# RCShield-v2.net
KiCad netlist of a schematic drawn in EAGLE
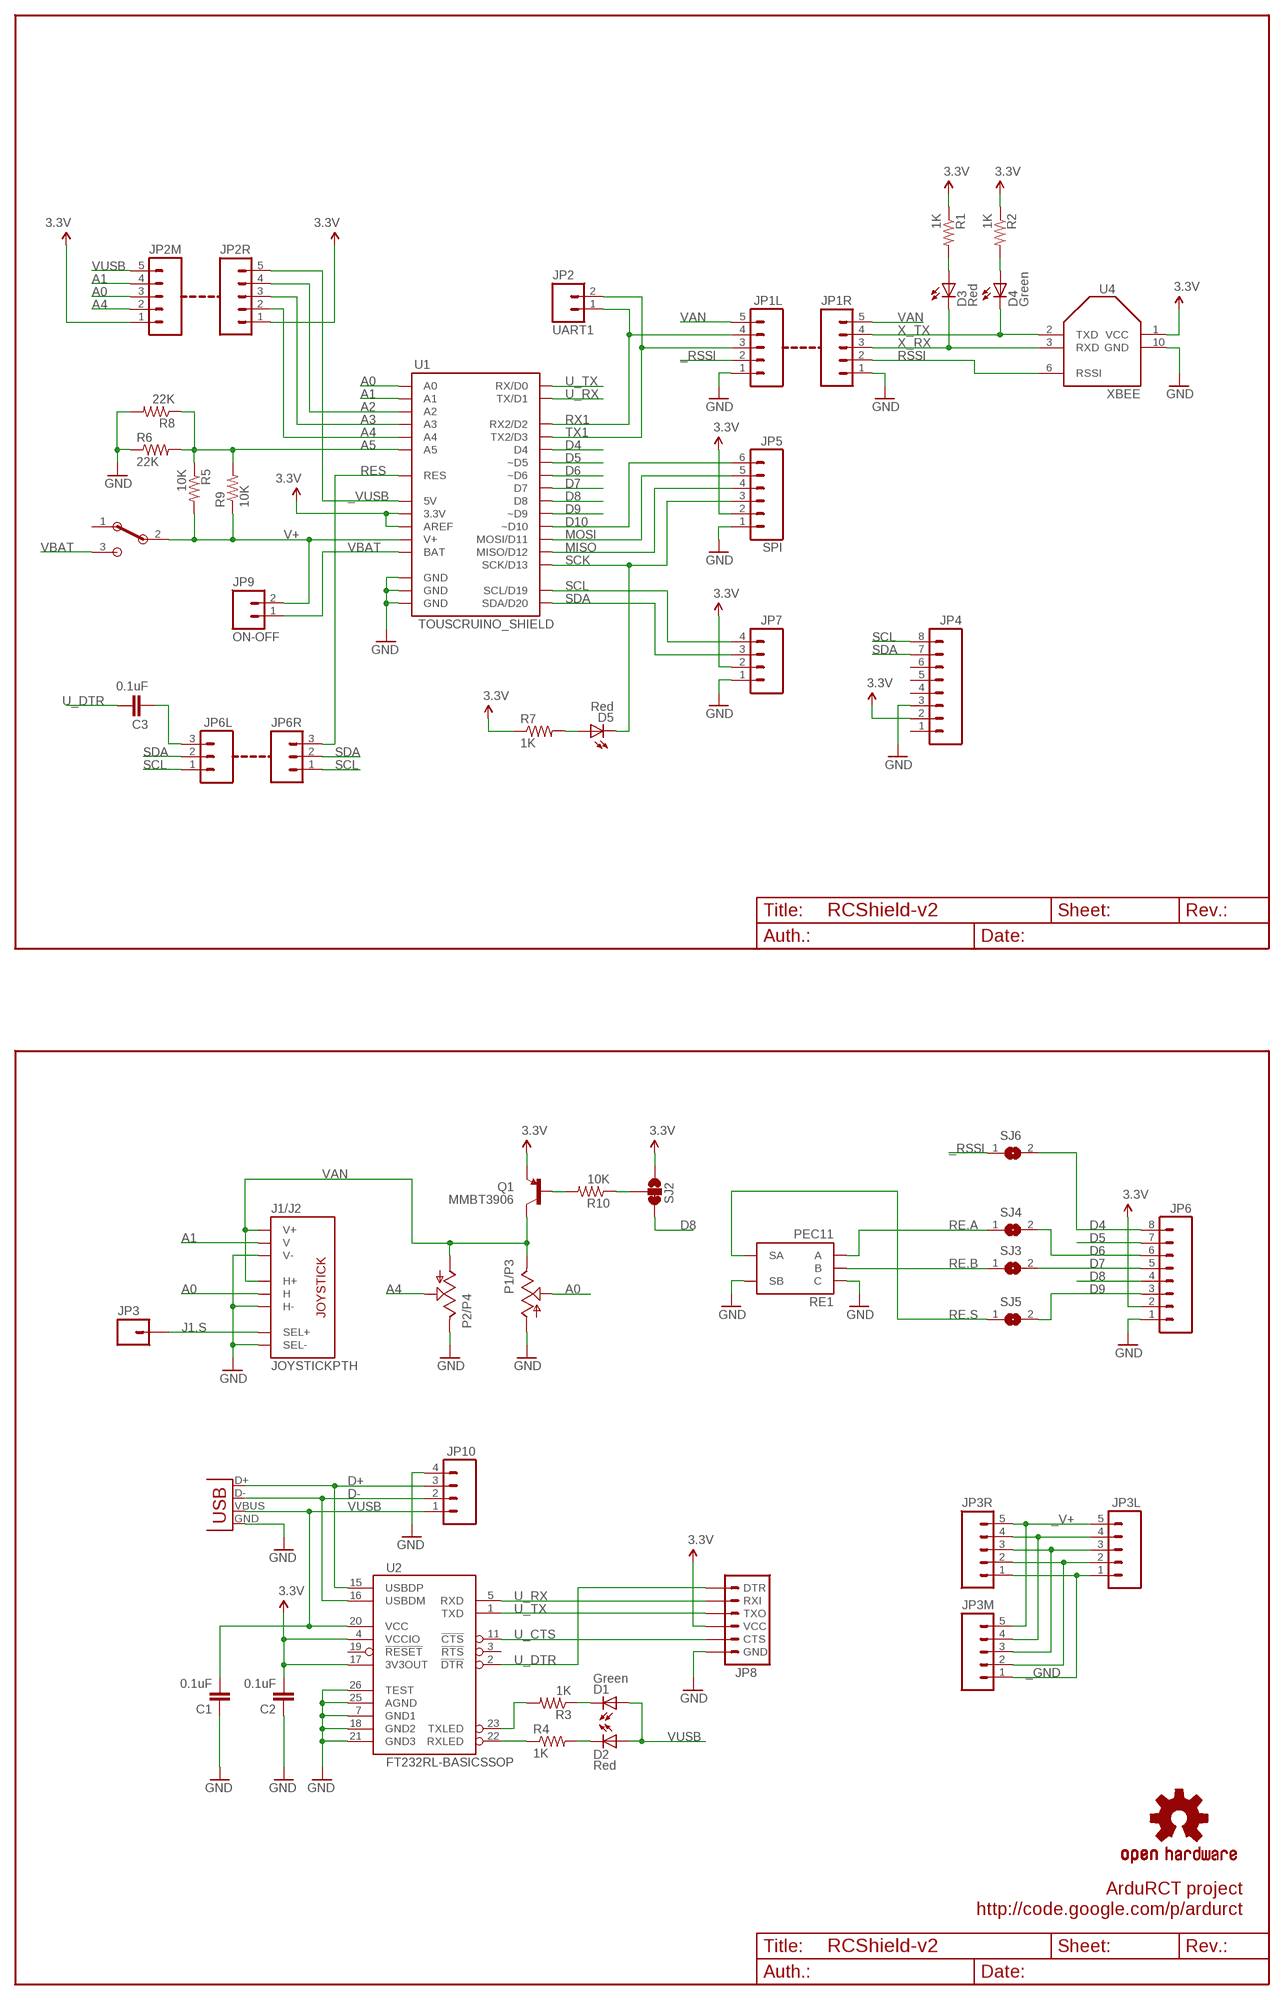
[diagram p0: schematic, sheet 1]

(export (version "E")
  (design (tool "Eeschema 10.0.6"))
  (components
    (comp (ref "C1")
      (value "0.1uF")
      (footprint "eagle-import:0805")
      (libsource (lib "eagle-import") (part "CAP0805"))
    )
    (comp (ref "C2")
      (value "0.1uF")
      (footprint "eagle-import:0805")
      (libsource (lib "eagle-import") (part "CAP0805"))
    )
    (comp (ref "C3")
      (value "0.1uF")
      (footprint "eagle-import:0805")
      (libsource (lib "eagle-import") (part "CAP0805"))
    )
    (comp (ref "D1")
      (value "Green")
      (footprint "eagle-import:LED")
      (libsource (lib "eagle-import") (part "LED"))
    )
    (comp (ref "D2")
      (value "Red")
      (footprint "eagle-import:LED")
      (libsource (lib "eagle-import") (part "LED"))
    )
    (comp (ref "D3")
      (value "Red")
      (footprint "eagle-import:LED")
      (libsource (lib "eagle-import") (part "LED"))
    )
    (comp (ref "D4")
      (value "Green")
      (footprint "eagle-import:LED")
      (libsource (lib "eagle-import") (part "LED"))
    )
    (comp (ref "D5")
      (value "Red")
      (footprint "eagle-import:LED")
      (libsource (lib "eagle-import") (part "LED"))
    )
    (comp (ref "J1/J2")
      (value "JOYSTICKPTH")
      (footprint "eagle-import:JOYSTICK")
      (libsource (lib "eagle-import") (part "JOYSTICKPTH"))
    )
    (comp (ref "JP1L")
      (value "M05")
      (footprint "eagle-import:2+3")
      (libsource (lib "eagle-import") (part "M05"))
    )
    (comp (ref "JP1R")
      (value "M05")
      (footprint "eagle-import:2+3")
      (libsource (lib "eagle-import") (part "M05"))
    )
    (comp (ref "JP2")
      (value "UART1")
      (footprint "eagle-import:1X02")
      (libsource (lib "eagle-import") (part "M02"))
    )
    (comp (ref "JP2M")
      (value "M05")
      (footprint "eagle-import:2+3")
      (libsource (lib "eagle-import") (part "M05"))
    )
    (comp (ref "JP2R")
      (value "M05")
      (footprint "eagle-import:2+3")
      (libsource (lib "eagle-import") (part "M05"))
    )
    (comp (ref "JP3")
      (value "M01PTH")
      (footprint "eagle-import:1X01")
      (libsource (lib "eagle-import") (part "M01PTH"))
    )
    (comp (ref "JP3L")
      (value "M05")
      (footprint "eagle-import:2+3")
      (libsource (lib "eagle-import") (part "M05"))
    )
    (comp (ref "JP3M")
      (value "M05")
      (footprint "eagle-import:2+3")
      (libsource (lib "eagle-import") (part "M05"))
    )
    (comp (ref "JP3R")
      (value "M05")
      (footprint "eagle-import:2+3")
      (libsource (lib "eagle-import") (part "M05"))
    )
    (comp (ref "JP4")
      (value "M08")
      (footprint "eagle-import:1X08")
      (libsource (lib "eagle-import") (part "M08"))
    )
    (comp (ref "JP5")
      (value "SPI")
      (footprint "eagle-import:1X06")
      (libsource (lib "eagle-import") (part "M06SIP"))
    )
    (comp (ref "JP6")
      (value "M08")
      (footprint "eagle-import:1X08")
      (libsource (lib "eagle-import") (part "M08"))
    )
    (comp (ref "JP6L")
      (value "M03PTH")
      (footprint "eagle-import:1X03")
      (libsource (lib "eagle-import") (part "M03PTH"))
    )
    (comp (ref "JP6R")
      (value "M03PTH")
      (footprint "eagle-import:1X03")
      (libsource (lib "eagle-import") (part "M03PTH"))
    )
    (comp (ref "JP7")
      (value "M04")
      (footprint "eagle-import:1X04")
      (libsource (lib "eagle-import") (part "M04"))
    )
    (comp (ref "JP8")
      (value "ARDUINO_SERIAL_PROGRAM")
      (footprint "eagle-import:1X06_F")
      (libsource (lib "eagle-import") (part "ARDUINO_SERIAL_PROGRAM"))
    )
    (comp (ref "JP9")
      (value "ON-OFF")
      (footprint "eagle-import:1X02")
      (libsource (lib "eagle-import") (part "M02"))
    )
    (comp (ref "JP10")
      (value "M04")
      (footprint "eagle-import:1X04")
      (libsource (lib "eagle-import") (part "M04"))
    )
    (comp (ref "P1/P3")
      (value "POT")
      (footprint "eagle-import:ALPS_POT")
      (libsource (lib "eagle-import") (part "POT"))
    )
    (comp (ref "P2/P4")
      (value "POT")
      (footprint "eagle-import:ALPS_POT")
      (libsource (lib "eagle-import") (part "POT"))
    )
    (comp (ref "Q1")
      (value "MMBT3906")
      (footprint "eagle-import:SOT23-3")
      (libsource (lib "eagle-import") (part "TRANSISTOR_PNPSMD"))
    )
    (comp (ref "R1")
      (value "1K")
      (footprint "eagle-import:0805")
      (libsource (lib "eagle-import") (part "RESISTOR0805-RES"))
    )
    (comp (ref "R2")
      (value "1K")
      (footprint "eagle-import:0805")
      (libsource (lib "eagle-import") (part "RESISTOR0805-RES"))
    )
    (comp (ref "R3")
      (value "1K")
      (footprint "eagle-import:0805")
      (libsource (lib "eagle-import") (part "RESISTOR0805-RES"))
    )
    (comp (ref "R4")
      (value "1K")
      (footprint "eagle-import:0805")
      (libsource (lib "eagle-import") (part "RESISTOR0805-RES"))
    )
    (comp (ref "R5")
      (value "10K")
      (footprint "eagle-import:0805")
      (libsource (lib "eagle-import") (part "RESISTOR0805-RES"))
    )
    (comp (ref "R6")
      (value "22K")
      (footprint "eagle-import:0805")
      (libsource (lib "eagle-import") (part "RESISTOR0805-RES"))
    )
    (comp (ref "R7")
      (value "1K")
      (footprint "eagle-import:0805")
      (libsource (lib "eagle-import") (part "RESISTOR0805-RES"))
    )
    (comp (ref "R8")
      (value "22K")
      (footprint "eagle-import:0207_7")
      (libsource (lib "eagle-import") (part "R-US_0207/7"))
    )
    (comp (ref "R9")
      (value "10K")
      (footprint "eagle-import:0207_7")
      (libsource (lib "eagle-import") (part "R-US_0207/7"))
    )
    (comp (ref "R10")
      (value "10K")
      (footprint "eagle-import:0805")
      (libsource (lib "eagle-import") (part "RESISTOR0805-RES"))
    )
    (comp (ref "RE1")
      (value "PEC11")
      (footprint "eagle-import:PEC11")
      (libsource (lib "eagle-import") (part "PEC11"))
    )
    (comp (ref "S4")
      (value "EG1224")
      (footprint "eagle-import:EG1224")
      (libsource (lib "eagle-import") (part "EG1224"))
    )
    (comp (ref "SJ2")
      (value "SJ_2WAYS_1-2W")
      (footprint "eagle-import:SJ_2WAYS_1-2")
      (libsource (lib "eagle-import") (part "SJ_2WAYS_1-2W"))
    )
    (comp (ref "SJ3") (value "SJ") (footprint "eagle-import:SJ") (libsource (lib "eagle-import") (part "SJ")))
    (comp (ref "SJ4") (value "SJ") (footprint "eagle-import:SJ") (libsource (lib "eagle-import") (part "SJ")))
    (comp (ref "SJ5") (value "SJ") (footprint "eagle-import:SJ") (libsource (lib "eagle-import") (part "SJ")))
    (comp (ref "SJ6") (value "SJ") (footprint "eagle-import:SJ") (libsource (lib "eagle-import") (part "SJ")))
    (comp (ref "U$1")
      (value "OSHW-LOGOM")
      (footprint "eagle-import:OSHW-LOGO-M")
      (libsource (lib "eagle-import") (part "OSHW-LOGOM"))
    )
    (comp (ref "U1")
      (value "TOUSCRUINO_SHIELD")
      (footprint "eagle-import:TOUSCRUINO_SHIELD_SPLIT")
      (libsource (lib "eagle-import") (part "TOUSCRUINO_SHIELDSPLIT"))
    )
    (comp (ref "U2")
      (value "FT232RL-BASICSSOP")
      (footprint "eagle-import:SSOP28DB")
      (libsource (lib "eagle-import") (part "FT232RL-BASICSSOP"))
    )
    (comp (ref "U4")
      (value "XBEE")
      (footprint "eagle-import:XBEE-SMD")
      (libsource (lib "eagle-import") (part "XBEE-RSSI"))
    )
    (comp (ref "X1")
      (value "USBSMD")
      (footprint "eagle-import:USB-MINIB")
      (libsource (lib "eagle-import") (part "USBSMD"))
    )
  )
  (nets
    (net (code "1") (name "/A0") (class "Default")
      (node (ref "J1/J2") (pin "H2") (pinfunction "H_H2") (pintype "bidirectional"))
      (node (ref "JP2M") (pin "3") (pinfunction "3_3") (pintype "passive"))
      (node (ref "P1/P3") (pin "P$2") (pinfunction "S_P$2") (pintype "passive"))
      (node (ref "U1") (pin "A0") (pinfunction "A0_A0") (pintype "bidirectional"))
    )
    (net (code "2") (name "/A1") (class "Default")
      (node (ref "J1/J2") (pin "V2") (pinfunction "V_V2") (pintype "bidirectional"))
      (node (ref "JP2M") (pin "4") (pinfunction "4_4") (pintype "passive"))
      (node (ref "U1") (pin "A1") (pinfunction "A1_A1") (pintype "bidirectional"))
    )
    (net (code "3") (name "/A2") (class "Default")
      (node (ref "JP2R") (pin "4") (pinfunction "4_4") (pintype "passive"))
      (node (ref "U1") (pin "A2") (pinfunction "A2_A2") (pintype "bidirectional"))
    )
    (net (code "4") (name "/A3") (class "Default")
      (node (ref "JP2R") (pin "3") (pinfunction "3_3") (pintype "passive"))
      (node (ref "U1") (pin "A3") (pinfunction "A3_A3") (pintype "bidirectional"))
    )
    (net (code "5") (name "/A4") (class "Default")
      (node (ref "JP2M") (pin "2") (pinfunction "2_2") (pintype "passive"))
      (node (ref "JP2R") (pin "2") (pinfunction "2_2") (pintype "passive"))
      (node (ref "P2/P4") (pin "P$2") (pinfunction "S_P$2") (pintype "passive"))
      (node (ref "U1") (pin "A4") (pinfunction "A4_A4") (pintype "bidirectional"))
    )
    (net (code "6") (name "/A5") (class "Default")
      (node (ref "R5") (pin "1") (pinfunction "1_1") (pintype "passive"))
      (node (ref "R6") (pin "2") (pinfunction "2_2") (pintype "passive"))
      (node (ref "R8") (pin "1") (pinfunction "1_1") (pintype "passive"))
      (node (ref "R9") (pin "2") (pinfunction "2_2") (pintype "passive"))
      (node (ref "U1") (pin "A5") (pinfunction "A5_A5") (pintype "bidirectional"))
    )
    (net (code "7") (name "/D+") (class "Default")
      (node (ref "JP10") (pin "3") (pinfunction "3_3") (pintype "passive"))
      (node (ref "U2") (pin "15") (pinfunction "USBDP_15") (pintype "bidirectional"))
      (node (ref "X1") (pin "D+") (pinfunction "D+_D+") (pintype "bidirectional"))
    )
    (net (code "8") (name "/D-") (class "Default")
      (node (ref "JP10") (pin "2") (pinfunction "2_2") (pintype "passive"))
      (node (ref "U2") (pin "16") (pinfunction "USBDM_16") (pintype "bidirectional"))
      (node (ref "X1") (pin "D-") (pinfunction "D-_D-") (pintype "bidirectional"))
    )
    (net (code "9") (name "/D4") (class "Default")
      (node (ref "JP6") (pin "8") (pinfunction "8_8") (pintype "passive"))
      (node (ref "SJ6") (pin "2") (pinfunction "2_2") (pintype "passive"))
      (node (ref "U1") (pin "D4") (pinfunction "D4_D4") (pintype "bidirectional"))
    )
    (net (code "10") (name "/D5") (class "Default")
      (node (ref "JP6") (pin "7") (pinfunction "7_7") (pintype "passive"))
      (node (ref "U1") (pin "D5") (pinfunction "~{D5}_D5") (pintype "bidirectional"))
    )
    (net (code "11") (name "/D6") (class "Default")
      (node (ref "JP6") (pin "6") (pinfunction "6_6") (pintype "passive"))
      (node (ref "SJ4") (pin "2") (pinfunction "2_2") (pintype "passive"))
      (node (ref "U1") (pin "D6") (pinfunction "~{D6}_D6") (pintype "bidirectional"))
    )
    (net (code "12") (name "/D7") (class "Default")
      (node (ref "JP6") (pin "5") (pinfunction "5_5") (pintype "passive"))
      (node (ref "SJ3") (pin "2") (pinfunction "2_2") (pintype "passive"))
      (node (ref "U1") (pin "D7") (pinfunction "D7_D7") (pintype "bidirectional"))
    )
    (net (code "13") (name "/D8") (class "Default")
      (node (ref "JP6") (pin "4") (pinfunction "4_4") (pintype "passive"))
      (node (ref "SJ2") (pin "1") (pinfunction "1_1") (pintype "passive"))
      (node (ref "U1") (pin "D8") (pinfunction "D8_D8") (pintype "bidirectional"))
    )
    (net (code "14") (name "/D9") (class "Default")
      (node (ref "JP6") (pin "3") (pinfunction "3_3") (pintype "passive"))
      (node (ref "SJ5") (pin "2") (pinfunction "2_2") (pintype "passive"))
      (node (ref "U1") (pin "D9") (pinfunction "~{D9}_D9") (pintype "bidirectional"))
    )
    (net (code "15") (name "/D10") (class "Default")
      (node (ref "JP5") (pin "6") (pinfunction "6_6") (pintype "passive"))
      (node (ref "U1") (pin "D10") (pinfunction "~{D10}_D10") (pintype "bidirectional"))
    )
    (net (code "16") (name "/J1.S") (class "Default")
      (node (ref "J1/J2") (pin "B1A") (pinfunction "SEL+_B1A") (pintype "bidirectional"))
      (node (ref "JP3") (pin "1") (pinfunction "1_1") (pintype "passive"))
    )
    (net (code "17") (name "/MISO") (class "Default")
      (node (ref "JP5") (pin "4") (pinfunction "4_4") (pintype "passive"))
      (node (ref "U1") (pin "D12") (pinfunction "MISO/D12_D12") (pintype "bidirectional"))
    )
    (net (code "18") (name "/MOSI") (class "Default")
      (node (ref "JP5") (pin "5") (pinfunction "5_5") (pintype "passive"))
      (node (ref "U1") (pin "D11") (pinfunction "MOSI/D11_D11") (pintype "bidirectional"))
    )
    (net (code "19") (name "/RE.A") (class "Default")
      (node (ref "RE1") (pin "A") (pinfunction "A_A") (pintype "bidirectional"))
      (node (ref "SJ4") (pin "1") (pinfunction "1_1") (pintype "passive"))
    )
    (net (code "20") (name "/RE.B") (class "Default")
      (node (ref "RE1") (pin "B") (pinfunction "B_B") (pintype "bidirectional"))
      (node (ref "SJ3") (pin "1") (pinfunction "1_1") (pintype "passive"))
    )
    (net (code "21") (name "/RE.S") (class "Default")
      (node (ref "RE1") (pin "S1") (pinfunction "SA_S1") (pintype "bidirectional"))
      (node (ref "SJ5") (pin "1") (pinfunction "1_1") (pintype "passive"))
    )
    (net (code "22") (name "/RES") (class "Default")
      (node (ref "JP6R") (pin "3") (pinfunction "3_3") (pintype "passive"))
      (node (ref "U1") (pin "RES") (pinfunction "RES_RES") (pintype "bidirectional"))
    )
    (net (code "23") (name "/RSSI") (class "Default")
      (node (ref "JP1R") (pin "2") (pinfunction "2_2") (pintype "passive"))
      (node (ref "U4") (pin "6") (pinfunction "RSSI_6") (pintype "bidirectional"))
    )
    (net (code "24") (name "/RX1") (class "Default")
      (node (ref "JP1L") (pin "4") (pinfunction "4_4") (pintype "passive"))
      (node (ref "JP2") (pin "1") (pinfunction "1_1") (pintype "passive"))
      (node (ref "U1") (pin "D2") (pinfunction "RX2/D2_D2") (pintype "bidirectional"))
    )
    (net (code "25") (name "/SCK") (class "Default")
      (node (ref "D5") (pin "C1") (pinfunction "C_C1") (pintype "passive"))
      (node (ref "JP5") (pin "3") (pinfunction "3_3") (pintype "passive"))
      (node (ref "U1") (pin "D13") (pinfunction "SCK/D13_D13") (pintype "bidirectional"))
    )
    (net (code "26") (name "/SCL") (class "Default")
      (node (ref "JP4") (pin "8") (pinfunction "8_8") (pintype "passive"))
      (node (ref "JP6L") (pin "1") (pinfunction "1_1") (pintype "passive"))
      (node (ref "JP6R") (pin "1") (pinfunction "1_1") (pintype "passive"))
      (node (ref "JP7") (pin "4") (pinfunction "4_4") (pintype "passive"))
      (node (ref "U1") (pin "SCL") (pinfunction "SCL/D19_SCL") (pintype "bidirectional"))
    )
    (net (code "27") (name "/SDA") (class "Default")
      (node (ref "JP4") (pin "7") (pinfunction "7_7") (pintype "passive"))
      (node (ref "JP6L") (pin "2") (pinfunction "2_2") (pintype "passive"))
      (node (ref "JP6R") (pin "2") (pinfunction "2_2") (pintype "passive"))
      (node (ref "JP7") (pin "3") (pinfunction "3_3") (pintype "passive"))
      (node (ref "U1") (pin "SDA") (pinfunction "SDA/D20_SDA") (pintype "bidirectional"))
    )
    (net (code "28") (name "/TX1") (class "Default")
      (node (ref "JP1L") (pin "3") (pinfunction "3_3") (pintype "passive"))
      (node (ref "JP2") (pin "2") (pinfunction "2_2") (pintype "passive"))
      (node (ref "U1") (pin "D3") (pinfunction "TX2/D3_D3") (pintype "bidirectional"))
    )
    (net (code "29") (name "/U_CTS") (class "Default")
      (node (ref "JP8") (pin "5") (pinfunction "CTS_5") (pintype "passive"))
      (node (ref "U2") (pin "11") (pinfunction "~{CTS}_11") (pintype "bidirectional"))
    )
    (net (code "30") (name "/U_DTR") (class "Default")
      (node (ref "C3") (pin "1") (pinfunction "1_1") (pintype "passive"))
      (node (ref "JP8") (pin "1") (pinfunction "DTR_1") (pintype "passive"))
      (node (ref "U2") (pin "2") (pinfunction "~{DTR}_2") (pintype "bidirectional"))
    )
    (net (code "31") (name "/U_RX") (class "Default")
      (node (ref "JP8") (pin "2") (pinfunction "RXI_2") (pintype "passive"))
      (node (ref "U1") (pin "TX") (pinfunction "TX/D1_TX") (pintype "bidirectional"))
      (node (ref "U2") (pin "5") (pinfunction "RXD_5") (pintype "input"))
    )
    (net (code "32") (name "/U_TX") (class "Default")
      (node (ref "JP8") (pin "3") (pinfunction "TXO_3") (pintype "passive"))
      (node (ref "U1") (pin "RX") (pinfunction "RX/D0_RX") (pintype "bidirectional"))
      (node (ref "U2") (pin "1") (pinfunction "TXD_1") (pintype "output"))
    )
    (net (code "33") (name "/V+") (class "Default")
      (node (ref "JP9") (pin "2") (pinfunction "2_2") (pintype "passive"))
      (node (ref "R5") (pin "2") (pinfunction "2_2") (pintype "passive"))
      (node (ref "R9") (pin "1") (pinfunction "1_1") (pintype "passive"))
      (node (ref "S4") (pin "2") (pinfunction "2_2") (pintype "bidirectional"))
      (node (ref "U1") (pin "V+") (pinfunction "V+_V+") (pintype "bidirectional"))
    )
    (net (code "34") (name "/VAN") (class "Default")
      (node (ref "J1/J2") (pin "H1") (pinfunction "H+_H1") (pintype "bidirectional"))
      (node (ref "J1/J2") (pin "V1") (pinfunction "V+_V1") (pintype "bidirectional"))
      (node (ref "JP1L") (pin "5") (pinfunction "5_5") (pintype "passive"))
      (node (ref "JP1R") (pin "5") (pinfunction "5_5") (pintype "passive"))
      (node (ref "P1/P3") (pin "P$1") (pinfunction "E_P$1") (pintype "passive"))
      (node (ref "P2/P4") (pin "P$3") (pinfunction "A_P$3") (pintype "passive"))
      (node (ref "Q1") (pin "3") (pinfunction "C_3") (pintype "passive"))
    )
    (net (code "35") (name "/VBAT") (class "Default")
      (node (ref "JP9") (pin "1") (pinfunction "1_1") (pintype "passive"))
      (node (ref "S4") (pin "3") (pinfunction "3_3") (pintype "bidirectional"))
      (node (ref "U1") (pin "BAT") (pinfunction "BAT_BAT") (pintype "bidirectional"))
    )
    (net (code "36") (name "/VUSB") (class "Default")
      (node (ref "C1") (pin "2") (pinfunction "2_2") (pintype "passive"))
      (node (ref "D1") (pin "A1") (pinfunction "A_A1") (pintype "passive"))
      (node (ref "D2") (pin "A1") (pinfunction "A_A1") (pintype "passive"))
      (node (ref "JP10") (pin "1") (pinfunction "1_1") (pintype "passive"))
      (node (ref "JP2M") (pin "5") (pinfunction "5_5") (pintype "passive"))
      (node (ref "U2") (pin "20") (pinfunction "VCC_20") (pintype "bidirectional"))
      (node (ref "X1") (pin "VBUS") (pinfunction "VBUS_VBUS") (pintype "bidirectional"))
    )
    (net (code "37") (name "/X_RX") (class "Default")
      (node (ref "D3") (pin "C1") (pinfunction "C_C1") (pintype "passive"))
      (node (ref "JP1R") (pin "3") (pinfunction "3_3") (pintype "passive"))
      (node (ref "U4") (pin "3") (pinfunction "RXD_3") (pintype "bidirectional"))
    )
    (net (code "38") (name "/X_TX") (class "Default")
      (node (ref "D4") (pin "C1") (pinfunction "C_C1") (pintype "passive"))
      (node (ref "JP1R") (pin "4") (pinfunction "4_4") (pintype "passive"))
      (node (ref "U4") (pin "2") (pinfunction "TXD_2") (pintype "bidirectional"))
    )
    (net (code "39") (name "/_GND") (class "Default")
      (node (ref "JP3L") (pin "1") (pinfunction "1_1") (pintype "passive"))
      (node (ref "JP3M") (pin "1") (pinfunction "1_1") (pintype "passive"))
      (node (ref "JP3R") (pin "1") (pinfunction "1_1") (pintype "passive"))
    )
    (net (code "40") (name "/_RSSI") (class "Default")
      (node (ref "JP1L") (pin "2") (pinfunction "2_2") (pintype "passive"))
      (node (ref "SJ6") (pin "1") (pinfunction "1_1") (pintype "passive"))
    )
    (net (code "41") (name "/_V+") (class "Default")
      (node (ref "JP3L") (pin "5") (pinfunction "5_5") (pintype "passive"))
      (node (ref "JP3M") (pin "5") (pinfunction "5_5") (pintype "passive"))
      (node (ref "JP3R") (pin "5") (pinfunction "5_5") (pintype "passive"))
    )
    (net (code "42") (name "/_VUSB") (class "Default")
      (node (ref "JP2R") (pin "5") (pinfunction "5_5") (pintype "passive"))
      (node (ref "U1") (pin "5V") (pinfunction "5V_5V") (pintype "bidirectional"))
    )
    (net (code "43") (name "3.3V") (class "Default")
      (node (ref "C2") (pin "2") (pinfunction "2_2") (pintype "passive"))
      (node (ref "JP2M") (pin "1") (pinfunction "1_1") (pintype "passive"))
      (node (ref "JP2R") (pin "1") (pinfunction "1_1") (pintype "passive"))
      (node (ref "JP4") (pin "2") (pinfunction "2_2") (pintype "passive"))
      (node (ref "JP5") (pin "2") (pinfunction "2_2") (pintype "passive"))
      (node (ref "JP6") (pin "2") (pinfunction "2_2") (pintype "passive"))
      (node (ref "JP7") (pin "2") (pinfunction "2_2") (pintype "passive"))
      (node (ref "JP8") (pin "4") (pinfunction "VCC_4") (pintype "passive"))
      (node (ref "Q1") (pin "2") (pinfunction "E_2") (pintype "passive"))
      (node (ref "R1") (pin "1") (pinfunction "1_1") (pintype "passive"))
      (node (ref "R2") (pin "1") (pinfunction "1_1") (pintype "passive"))
      (node (ref "R7") (pin "1") (pinfunction "1_1") (pintype "passive"))
      (node (ref "SJ2") (pin "3") (pinfunction "3_3") (pintype "passive"))
      (node (ref "U1") (pin "3.3V") (pinfunction "3.3V_3.3V") (pintype "bidirectional"))
      (node (ref "U1") (pin "AREF") (pinfunction "AREF_AREF") (pintype "bidirectional"))
      (node (ref "U2") (pin "17") (pinfunction "3V3OUT_17") (pintype "output"))
      (node (ref "U2") (pin "4") (pinfunction "VCCIO_4") (pintype "bidirectional"))
      (node (ref "U4") (pin "1") (pinfunction "VCC_1") (pintype "bidirectional"))
    )
    (net (code "44") (name "GND") (class "Default")
      (node (ref "C1") (pin "1") (pinfunction "1_1") (pintype "passive"))
      (node (ref "C2") (pin "1") (pinfunction "1_1") (pintype "passive"))
      (node (ref "J1/J2") (pin "B2A") (pinfunction "SEL-_B2A") (pintype "bidirectional"))
      (node (ref "J1/J2") (pin "H3") (pinfunction "H-_H3") (pintype "bidirectional"))
      (node (ref "J1/J2") (pin "V3") (pinfunction "V-_V3") (pintype "bidirectional"))
      (node (ref "JP10") (pin "4") (pinfunction "4_4") (pintype "passive"))
      (node (ref "JP1L") (pin "1") (pinfunction "1_1") (pintype "passive"))
      (node (ref "JP1R") (pin "1") (pinfunction "1_1") (pintype "passive"))
      (node (ref "JP4") (pin "3") (pinfunction "3_3") (pintype "passive"))
      (node (ref "JP5") (pin "1") (pinfunction "1_1") (pintype "passive"))
      (node (ref "JP6") (pin "1") (pinfunction "1_1") (pintype "passive"))
      (node (ref "JP7") (pin "1") (pinfunction "1_1") (pintype "passive"))
      (node (ref "JP8") (pin "6") (pinfunction "GND_6") (pintype "passive"))
      (node (ref "P1/P3") (pin "P$3") (pinfunction "A_P$3") (pintype "passive"))
      (node (ref "P2/P4") (pin "P$1") (pinfunction "E_P$1") (pintype "passive"))
      (node (ref "R6") (pin "1") (pinfunction "1_1") (pintype "passive"))
      (node (ref "R8") (pin "2") (pinfunction "2_2") (pintype "passive"))
      (node (ref "RE1") (pin "C") (pinfunction "C_C") (pintype "bidirectional"))
      (node (ref "RE1") (pin "S2") (pinfunction "SB_S2") (pintype "bidirectional"))
      (node (ref "U1") (pin "GND@0") (pinfunction "GND_GND@0") (pintype "bidirectional"))
      (node (ref "U1") (pin "GND@1") (pinfunction "GND_GND@1") (pintype "bidirectional"))
      (node (ref "U1") (pin "GND@2") (pinfunction "GND_GND@2") (pintype "bidirectional"))
      (node (ref "U2") (pin "18") (pinfunction "GND2_18") (pintype "bidirectional"))
      (node (ref "U2") (pin "21") (pinfunction "GND3_21") (pintype "bidirectional"))
      (node (ref "U2") (pin "25") (pinfunction "AGND_25") (pintype "bidirectional"))
      (node (ref "U2") (pin "26") (pinfunction "TEST_26") (pintype "input"))
      (node (ref "U2") (pin "7") (pinfunction "GND1_7") (pintype "bidirectional"))
      (node (ref "U4") (pin "10") (pinfunction "GND_10") (pintype "bidirectional"))
      (node (ref "X1") (pin "GND") (pinfunction "GND_GND") (pintype "bidirectional"))
    )
    (net (code "45") (name "Net-(C3-Pad2)") (class "Default")
      (node (ref "C3") (pin "2") (pinfunction "2_2") (pintype "passive"))
      (node (ref "JP6L") (pin "3") (pinfunction "3_3") (pintype "passive"))
    )
    (net (code "46") (name "Net-(D1-C)") (class "Default")
      (node (ref "D1") (pin "C1") (pinfunction "C_C1") (pintype "passive"))
      (node (ref "R3") (pin "1") (pinfunction "1_1") (pintype "passive"))
    )
    (net (code "47") (name "Net-(D2-C)") (class "Default")
      (node (ref "D2") (pin "C1") (pinfunction "C_C1") (pintype "passive"))
      (node (ref "R4") (pin "2") (pinfunction "2_2") (pintype "passive"))
    )
    (net (code "48") (name "Net-(D3-A)") (class "Default")
      (node (ref "D3") (pin "A1") (pinfunction "A_A1") (pintype "passive"))
      (node (ref "R1") (pin "2") (pinfunction "2_2") (pintype "passive"))
    )
    (net (code "49") (name "Net-(D4-A)") (class "Default")
      (node (ref "D4") (pin "A1") (pinfunction "A_A1") (pintype "passive"))
      (node (ref "R2") (pin "2") (pinfunction "2_2") (pintype "passive"))
    )
    (net (code "50") (name "Net-(D5-A)") (class "Default")
      (node (ref "D5") (pin "A1") (pinfunction "A_A1") (pintype "passive"))
      (node (ref "R7") (pin "2") (pinfunction "2_2") (pintype "passive"))
    )
    (net (code "51") (name "Net-(JP3L-Pad2)") (class "Default")
      (node (ref "JP3L") (pin "2") (pinfunction "2_2") (pintype "passive"))
      (node (ref "JP3M") (pin "2") (pinfunction "2_2") (pintype "passive"))
      (node (ref "JP3R") (pin "2") (pinfunction "2_2") (pintype "passive"))
    )
    (net (code "52") (name "Net-(JP3L-Pad3)") (class "Default")
      (node (ref "JP3L") (pin "3") (pinfunction "3_3") (pintype "passive"))
      (node (ref "JP3M") (pin "3") (pinfunction "3_3") (pintype "passive"))
      (node (ref "JP3R") (pin "3") (pinfunction "3_3") (pintype "passive"))
    )
    (net (code "53") (name "Net-(JP3L-Pad4)") (class "Default")
      (node (ref "JP3L") (pin "4") (pinfunction "4_4") (pintype "passive"))
      (node (ref "JP3M") (pin "4") (pinfunction "4_4") (pintype "passive"))
      (node (ref "JP3R") (pin "4") (pinfunction "4_4") (pintype "passive"))
    )
    (net (code "54") (name "Net-(Q1-B)") (class "Default")
      (node (ref "Q1") (pin "1") (pinfunction "B_1") (pintype "passive"))
      (node (ref "R10") (pin "2") (pinfunction "2_2") (pintype "passive"))
    )
    (net (code "55") (name "Net-(R10-Pad1)") (class "Default")
      (node (ref "R10") (pin "1") (pinfunction "1_1") (pintype "passive"))
      (node (ref "SJ2") (pin "2") (pinfunction "2_2") (pintype "passive"))
    )
    (net (code "56") (name "Net-(U2-RXLED)") (class "Default")
      (node (ref "R4") (pin "1") (pinfunction "1_1") (pintype "passive"))
      (node (ref "U2") (pin "22") (pinfunction "RXLED_22") (pintype "bidirectional"))
    )
    (net (code "57") (name "Net-(U2-TXLED)") (class "Default")
      (node (ref "R3") (pin "2") (pinfunction "2_2") (pintype "passive"))
      (node (ref "U2") (pin "23") (pinfunction "TXLED_23") (pintype "bidirectional"))
    )
    (net (code "58") (name "unconnected-(JP4-Pad1)") (class "Default")
      (node (ref "JP4") (pin "1") (pinfunction "1_1") (pintype "passive"))
    )
    (net (code "59") (name "unconnected-(JP4-Pad4)") (class "Default")
      (node (ref "JP4") (pin "4") (pinfunction "4_4") (pintype "passive"))
    )
    (net (code "60") (name "unconnected-(JP4-Pad5)") (class "Default")
      (node (ref "JP4") (pin "5") (pinfunction "5_5") (pintype "passive"))
    )
    (net (code "61") (name "unconnected-(JP4-Pad6)") (class "Default")
      (node (ref "JP4") (pin "6") (pinfunction "6_6") (pintype "passive"))
    )
    (net (code "62") (name "unconnected-(S4-Pad1)") (class "Default")
      (node (ref "S4") (pin "1") (pinfunction "1_1") (pintype "bidirectional"))
    )
    (net (code "63") (name "unconnected-(U2-~{RESET}-Pad19)") (class "Default")
      (node (ref "U2") (pin "19") (pinfunction "~{RESET}_19") (pintype "bidirectional"))
    )
    (net (code "64") (name "unconnected-(U2-~{RTS}-Pad3)") (class "Default")
      (node (ref "U2") (pin "3") (pinfunction "~{RTS}_3") (pintype "bidirectional"))
    )
  )
)
